# EasyEDA_board_SCH.net
KiCad netlist of a schematic drawn in EasyEDA
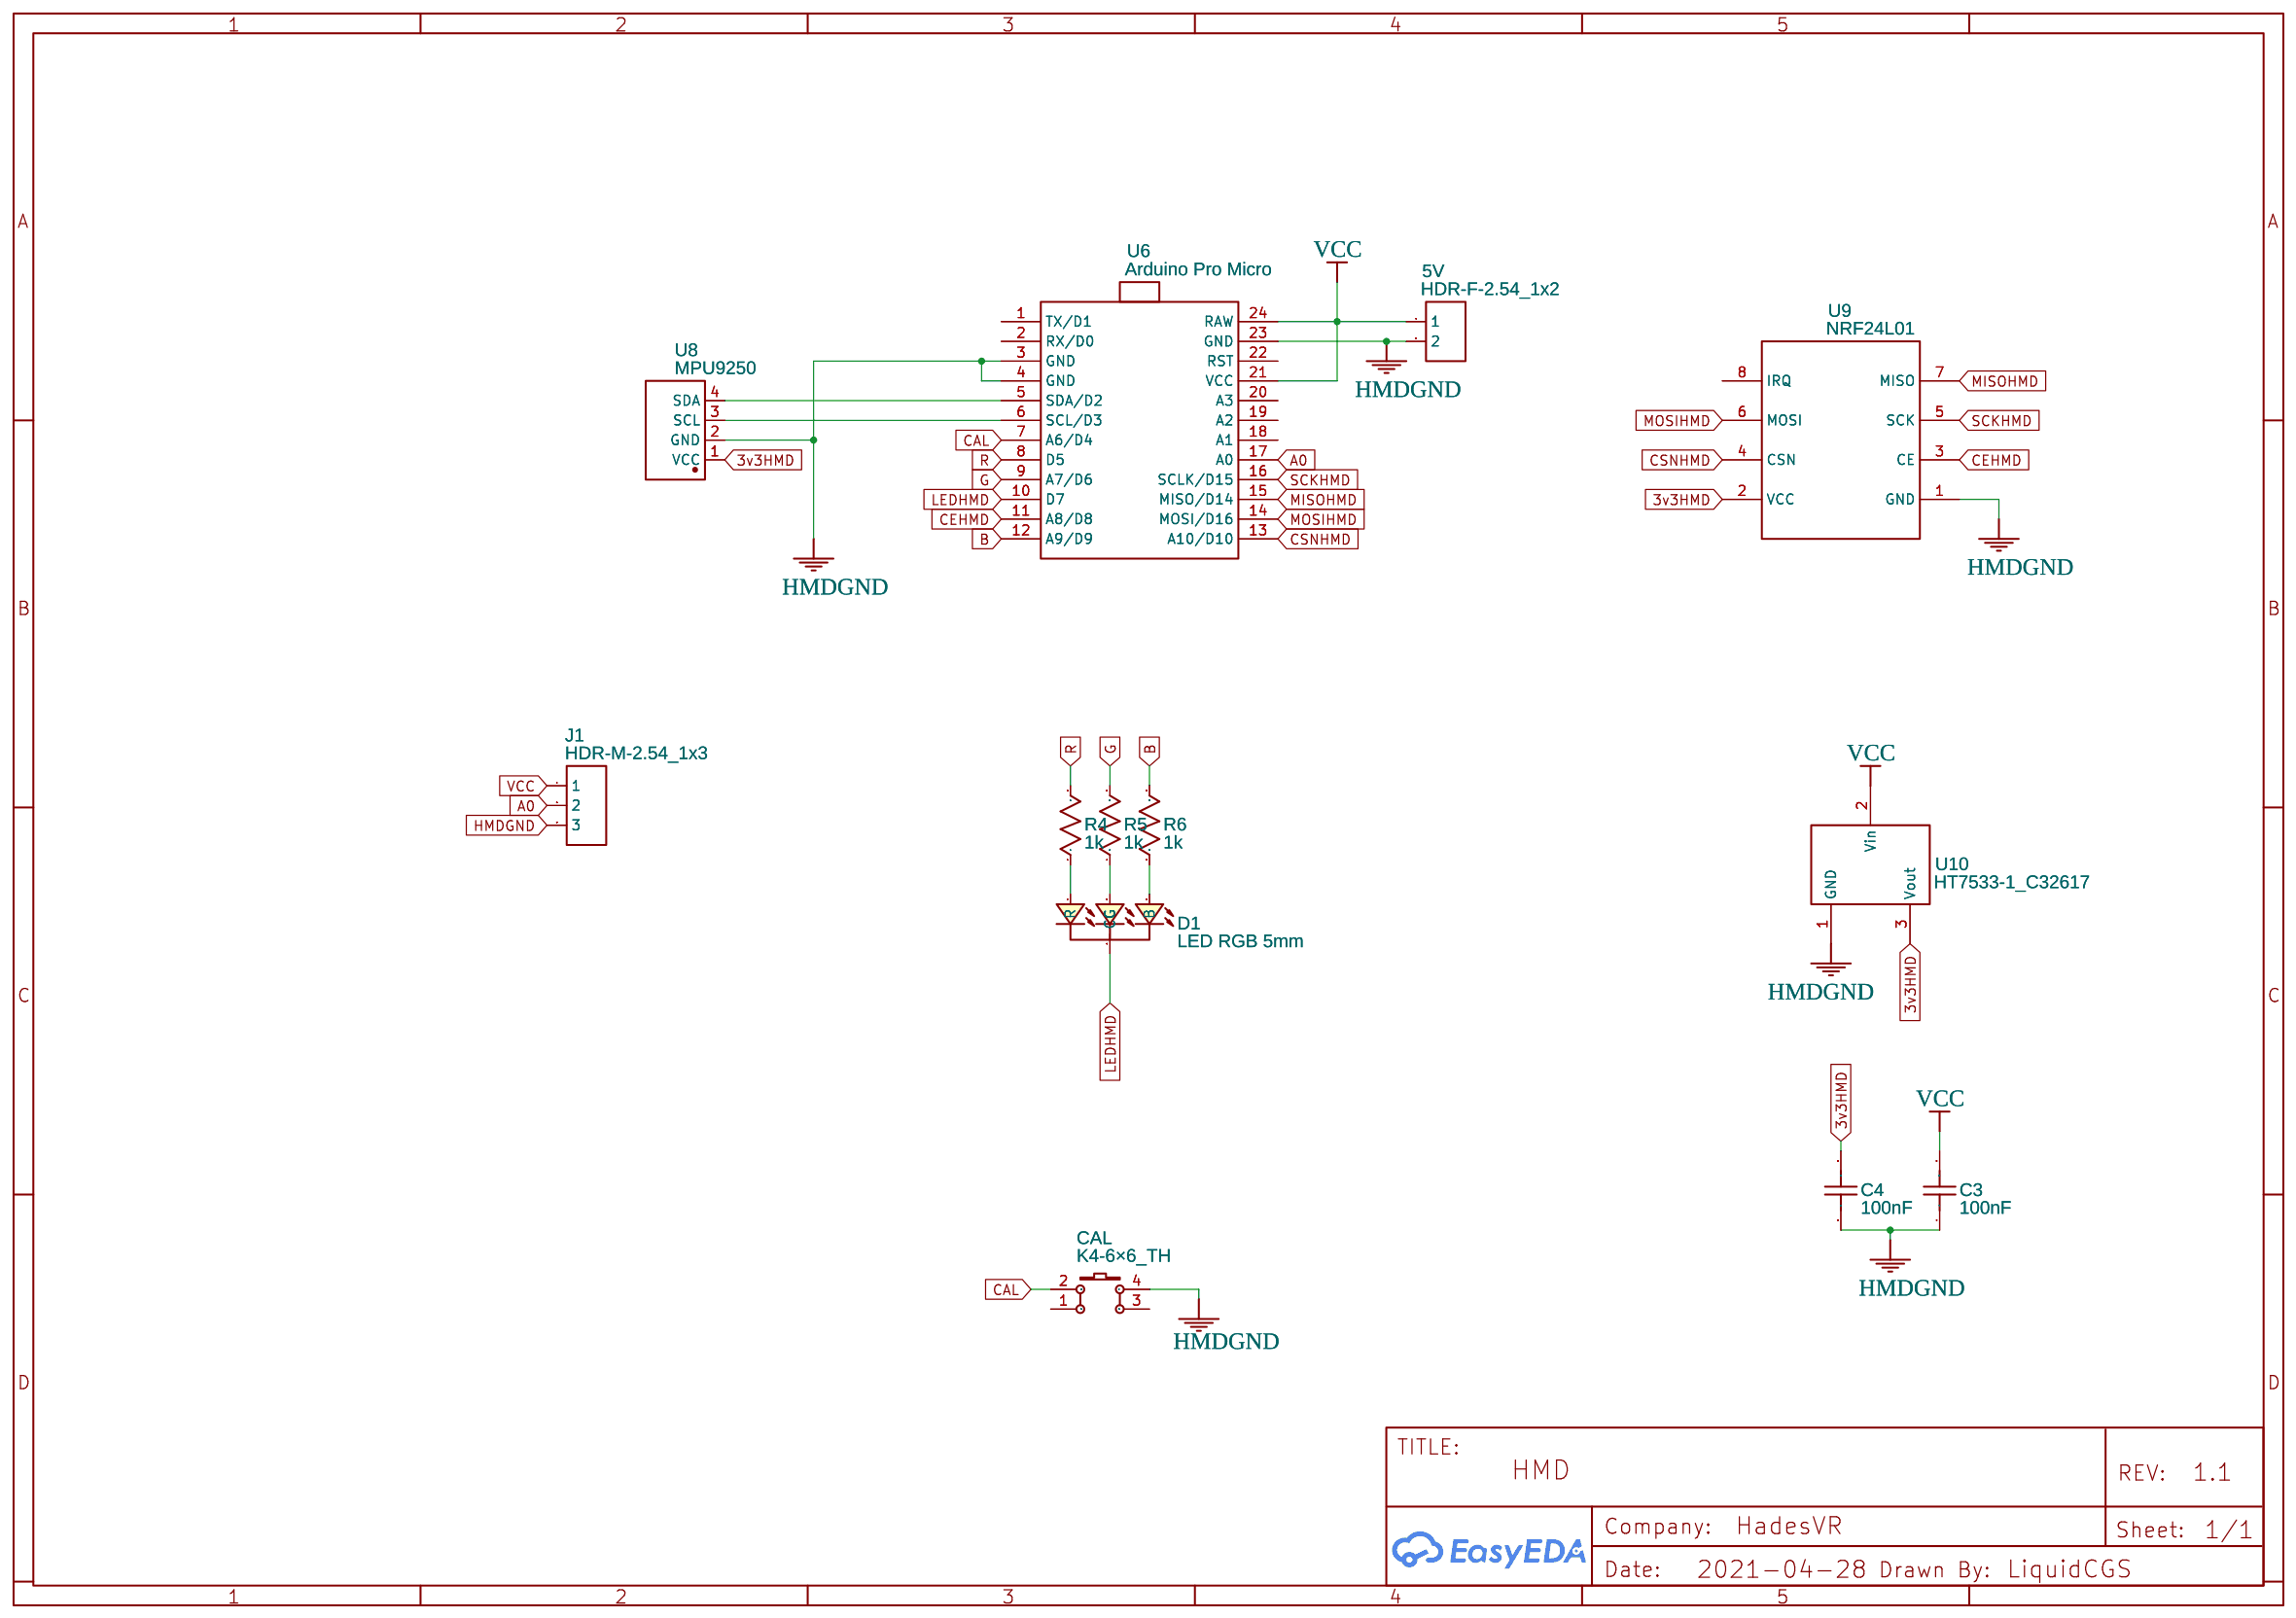
[diagram p0: schematic sheet]

(export (version "E")
  (design (tool "Eeschema 10.0.6"))
  (components
    (comp (ref "5V")
      (value "HDR-F-2.54_1x2")
      (fields (field (name "BOM_Supplier Part") "C49661"))
      (libsource (lib "") (part "HDR-F-2.54_1x2"))
    )
    (comp (ref "C3") (value "100nF") (libsource (lib "") (part "C_RAD-0.2_US")))
    (comp (ref "C4") (value "100nF") (libsource (lib "") (part "C_RAD-0.2_US")))
    (comp (ref "CAL")
      (value "K4-6×6_TH")
      (fields
        (field (name "BOM_Manufacturer Part") "K2-1102DP-E4SW-04")
        (field (name "BOM_Supplier Part") "C136684")
      )
      (libsource (lib "") (part "K4-6×6_TH"))
    )
    (comp (ref "D1")
      (value "LED RGB 5mm")
      (fields
        (field (name "BOM_Manufacturer Part") "TJ-L5FYTXHMCSLCRGB-A5")
        (field (name "BOM_Supplier Part") "C330759")
      )
      (libsource (lib "") (part "LED RGB 5mm"))
    )
    (comp (ref "J1")
      (value "HDR-M-2.54_1x3")
      (fields (field (name "BOM_Supplier Part") "C180248"))
      (libsource (lib "") (part "HDR-M-2.54_1x3"))
    )
    (comp (ref "R4") (value "1k") (libsource (lib "") (part "R_AXIAL-0.3_US")))
    (comp (ref "R5") (value "1k") (libsource (lib "") (part "R_AXIAL-0.3_US")))
    (comp (ref "R6") (value "1k") (libsource (lib "") (part "R_AXIAL-0.3_US")))
    (comp (ref "U6") (value "Arduino Pro Micro") (libsource (lib "") (part "Arduino Pro Micro")))
    (comp (ref "U8") (value "MPU9250") (libsource (lib "") (part "MPU9250")))
    (comp (ref "U9") (value "NRF24L01") (libsource (lib "") (part "NRF24L01")))
    (comp (ref "U10")
      (value "HT7533-1_C32617")
      (fields (field (name "BOM_Manufacturer Part") "HT7533-1") (field (name "BOM_Supplier Part") "C32617"))
      (libsource (lib "") (part "HT7533-1_C32617"))
    )
  )
  (nets
    (net (code "1") (name "3v3HMD") (class "Default")
      (node (ref "C4") (pin "2") (pinfunction "2_2") (pintype "unspecified"))
      (node (ref "U10") (pin "3") (pinfunction "Vout_3") (pintype "unspecified"))
      (node (ref "U8") (pin "1") (pinfunction "VCC_1") (pintype "unspecified"))
      (node (ref "U9") (pin "2") (pinfunction "VCC_2") (pintype "unspecified"))
    )
    (net (code "2") (name "A0") (class "Default")
      (node (ref "J1") (pin "2") (pinfunction "2_2") (pintype "input"))
      (node (ref "U6") (pin "17") (pinfunction "A0_17") (pintype "unspecified"))
    )
    (net (code "3") (name "B") (class "Default")
      (node (ref "R6") (pin "2") (pinfunction "2_2") (pintype "unspecified"))
      (node (ref "U6") (pin "12") (pinfunction "A9/D9_12") (pintype "unspecified"))
    )
    (net (code "4") (name "CAL") (class "Default")
      (node (ref "CAL") (pin "2") (pinfunction "2_2") (pintype "unspecified"))
      (node (ref "U6") (pin "7") (pinfunction "A6/D4_7") (pintype "unspecified"))
    )
    (net (code "5") (name "CEHMD") (class "Default")
      (node (ref "U6") (pin "11") (pinfunction "A8/D8_11") (pintype "unspecified"))
      (node (ref "U9") (pin "3") (pinfunction "CE_3") (pintype "unspecified"))
    )
    (net (code "6") (name "CSNHMD") (class "Default")
      (node (ref "U6") (pin "13") (pinfunction "A10/D10_13") (pintype "unspecified"))
      (node (ref "U9") (pin "4") (pinfunction "CSN_4") (pintype "unspecified"))
    )
    (net (code "7") (name "G") (class "Default")
      (node (ref "R5") (pin "2") (pinfunction "2_2") (pintype "unspecified"))
      (node (ref "U6") (pin "9") (pinfunction "A7/D6_9") (pintype "unspecified"))
    )
    (net (code "8") (name "HMDGND") (class "Default")
      (node (ref "5V") (pin "2") (pinfunction "2_2") (pintype "input"))
      (node (ref "C3") (pin "1") (pinfunction "1_1") (pintype "unspecified"))
      (node (ref "C4") (pin "1") (pinfunction "1_1") (pintype "unspecified"))
      (node (ref "CAL") (pin "4") (pinfunction "4_4") (pintype "unspecified"))
      (node (ref "J1") (pin "3") (pinfunction "3_3") (pintype "input"))
      (node (ref "U10") (pin "1") (pinfunction "GND_1") (pintype "unspecified"))
      (node (ref "U6") (pin "23") (pinfunction "GND_23") (pintype "unspecified"))
      (node (ref "U6") (pin "3") (pinfunction "GND_3") (pintype "unspecified"))
      (node (ref "U6") (pin "4") (pinfunction "GND_4") (pintype "unspecified"))
      (node (ref "U8") (pin "2") (pinfunction "GND_2") (pintype "unspecified"))
      (node (ref "U9") (pin "1") (pinfunction "GND_1") (pintype "unspecified"))
    )
    (net (code "9") (name "LEDHMD") (class "Default")
      (node (ref "D1") (pin "2") (pinfunction "CC_2") (pintype "unspecified"))
      (node (ref "U6") (pin "10") (pinfunction "D7_10") (pintype "unspecified"))
    )
    (net (code "10") (name "MISOHMD") (class "Default")
      (node (ref "U6") (pin "15") (pinfunction "MISO/D14_15") (pintype "unspecified"))
      (node (ref "U9") (pin "7") (pinfunction "MISO_7") (pintype "unspecified"))
    )
    (net (code "11") (name "MOSIHMD") (class "Default")
      (node (ref "U6") (pin "14") (pinfunction "MOSI/D16_14") (pintype "unspecified"))
      (node (ref "U9") (pin "6") (pinfunction "MOSI_6") (pintype "unspecified"))
    )
    (net (code "12") (name "Net-(D1-B)") (class "Default")
      (node (ref "D1") (pin "4") (pinfunction "B_4") (pintype "unspecified"))
      (node (ref "R6") (pin "1") (pinfunction "1_1") (pintype "unspecified"))
    )
    (net (code "13") (name "Net-(D1-G)") (class "Default")
      (node (ref "D1") (pin "3") (pinfunction "G_3") (pintype "unspecified"))
      (node (ref "R5") (pin "1") (pinfunction "1_1") (pintype "unspecified"))
    )
    (net (code "14") (name "Net-(D1-R)") (class "Default")
      (node (ref "D1") (pin "1") (pinfunction "R_1") (pintype "unspecified"))
      (node (ref "R4") (pin "1") (pinfunction "1_1") (pintype "unspecified"))
    )
    (net (code "15") (name "Net-(U6-SCL{slash}D3)") (class "Default")
      (node (ref "U6") (pin "6") (pinfunction "SCL/D3_6") (pintype "unspecified"))
      (node (ref "U8") (pin "3") (pinfunction "SCL_3") (pintype "unspecified"))
    )
    (net (code "16") (name "Net-(U6-SDA{slash}D2)") (class "Default")
      (node (ref "U6") (pin "5") (pinfunction "SDA/D2_5") (pintype "unspecified"))
      (node (ref "U8") (pin "4") (pinfunction "SDA_4") (pintype "unspecified"))
    )
    (net (code "17") (name "R") (class "Default")
      (node (ref "R4") (pin "2") (pinfunction "2_2") (pintype "unspecified"))
      (node (ref "U6") (pin "8") (pinfunction "D5_8") (pintype "unspecified"))
    )
    (net (code "18") (name "SCKHMD") (class "Default")
      (node (ref "U6") (pin "16") (pinfunction "SCLK/D15_16") (pintype "unspecified"))
      (node (ref "U9") (pin "5") (pinfunction "SCK_5") (pintype "unspecified"))
    )
    (net (code "19") (name "VCC") (class "Default")
      (node (ref "5V") (pin "1") (pinfunction "1_1") (pintype "input"))
      (node (ref "C3") (pin "2") (pinfunction "2_2") (pintype "unspecified"))
      (node (ref "J1") (pin "1") (pinfunction "1_1") (pintype "input"))
      (node (ref "U10") (pin "2") (pinfunction "Vin_2") (pintype "unspecified"))
      (node (ref "U6") (pin "21") (pinfunction "VCC_21") (pintype "unspecified"))
      (node (ref "U6") (pin "24") (pinfunction "RAW_24") (pintype "unspecified"))
    )
    (net (code "20") (name "unconnected-(CAL-Pad1)") (class "Default")
      (node (ref "CAL") (pin "1") (pinfunction "1_1") (pintype "unspecified"))
    )
    (net (code "21") (name "unconnected-(CAL-Pad3)") (class "Default")
      (node (ref "CAL") (pin "3") (pinfunction "3_3") (pintype "unspecified"))
    )
    (net (code "22") (name "unconnected-(U6-A1-Pad18)") (class "Default")
      (node (ref "U6") (pin "18") (pinfunction "A1_18") (pintype "unspecified"))
    )
    (net (code "23") (name "unconnected-(U6-A2-Pad19)") (class "Default")
      (node (ref "U6") (pin "19") (pinfunction "A2_19") (pintype "unspecified"))
    )
    (net (code "24") (name "unconnected-(U6-A3-Pad20)") (class "Default")
      (node (ref "U6") (pin "20") (pinfunction "A3_20") (pintype "unspecified"))
    )
    (net (code "25") (name "unconnected-(U6-RST-Pad22)") (class "Default")
      (node (ref "U6") (pin "22") (pinfunction "RST_22") (pintype "unspecified"))
    )
    (net (code "26") (name "unconnected-(U6-RX{slash}D0-Pad2)") (class "Default")
      (node (ref "U6") (pin "2") (pinfunction "RX/D0_2") (pintype "unspecified"))
    )
    (net (code "27") (name "unconnected-(U6-TX{slash}D1-Pad1)") (class "Default")
      (node (ref "U6") (pin "1") (pinfunction "TX/D1_1") (pintype "unspecified"))
    )
    (net (code "28") (name "unconnected-(U9-IRQ-Pad8)") (class "Default")
      (node (ref "U9") (pin "8") (pinfunction "IRQ_8") (pintype "unspecified"))
    )
  )
)
